# voltage_sensor_v0_4.net
KiCad netlist of a schematic drawn in EAGLE
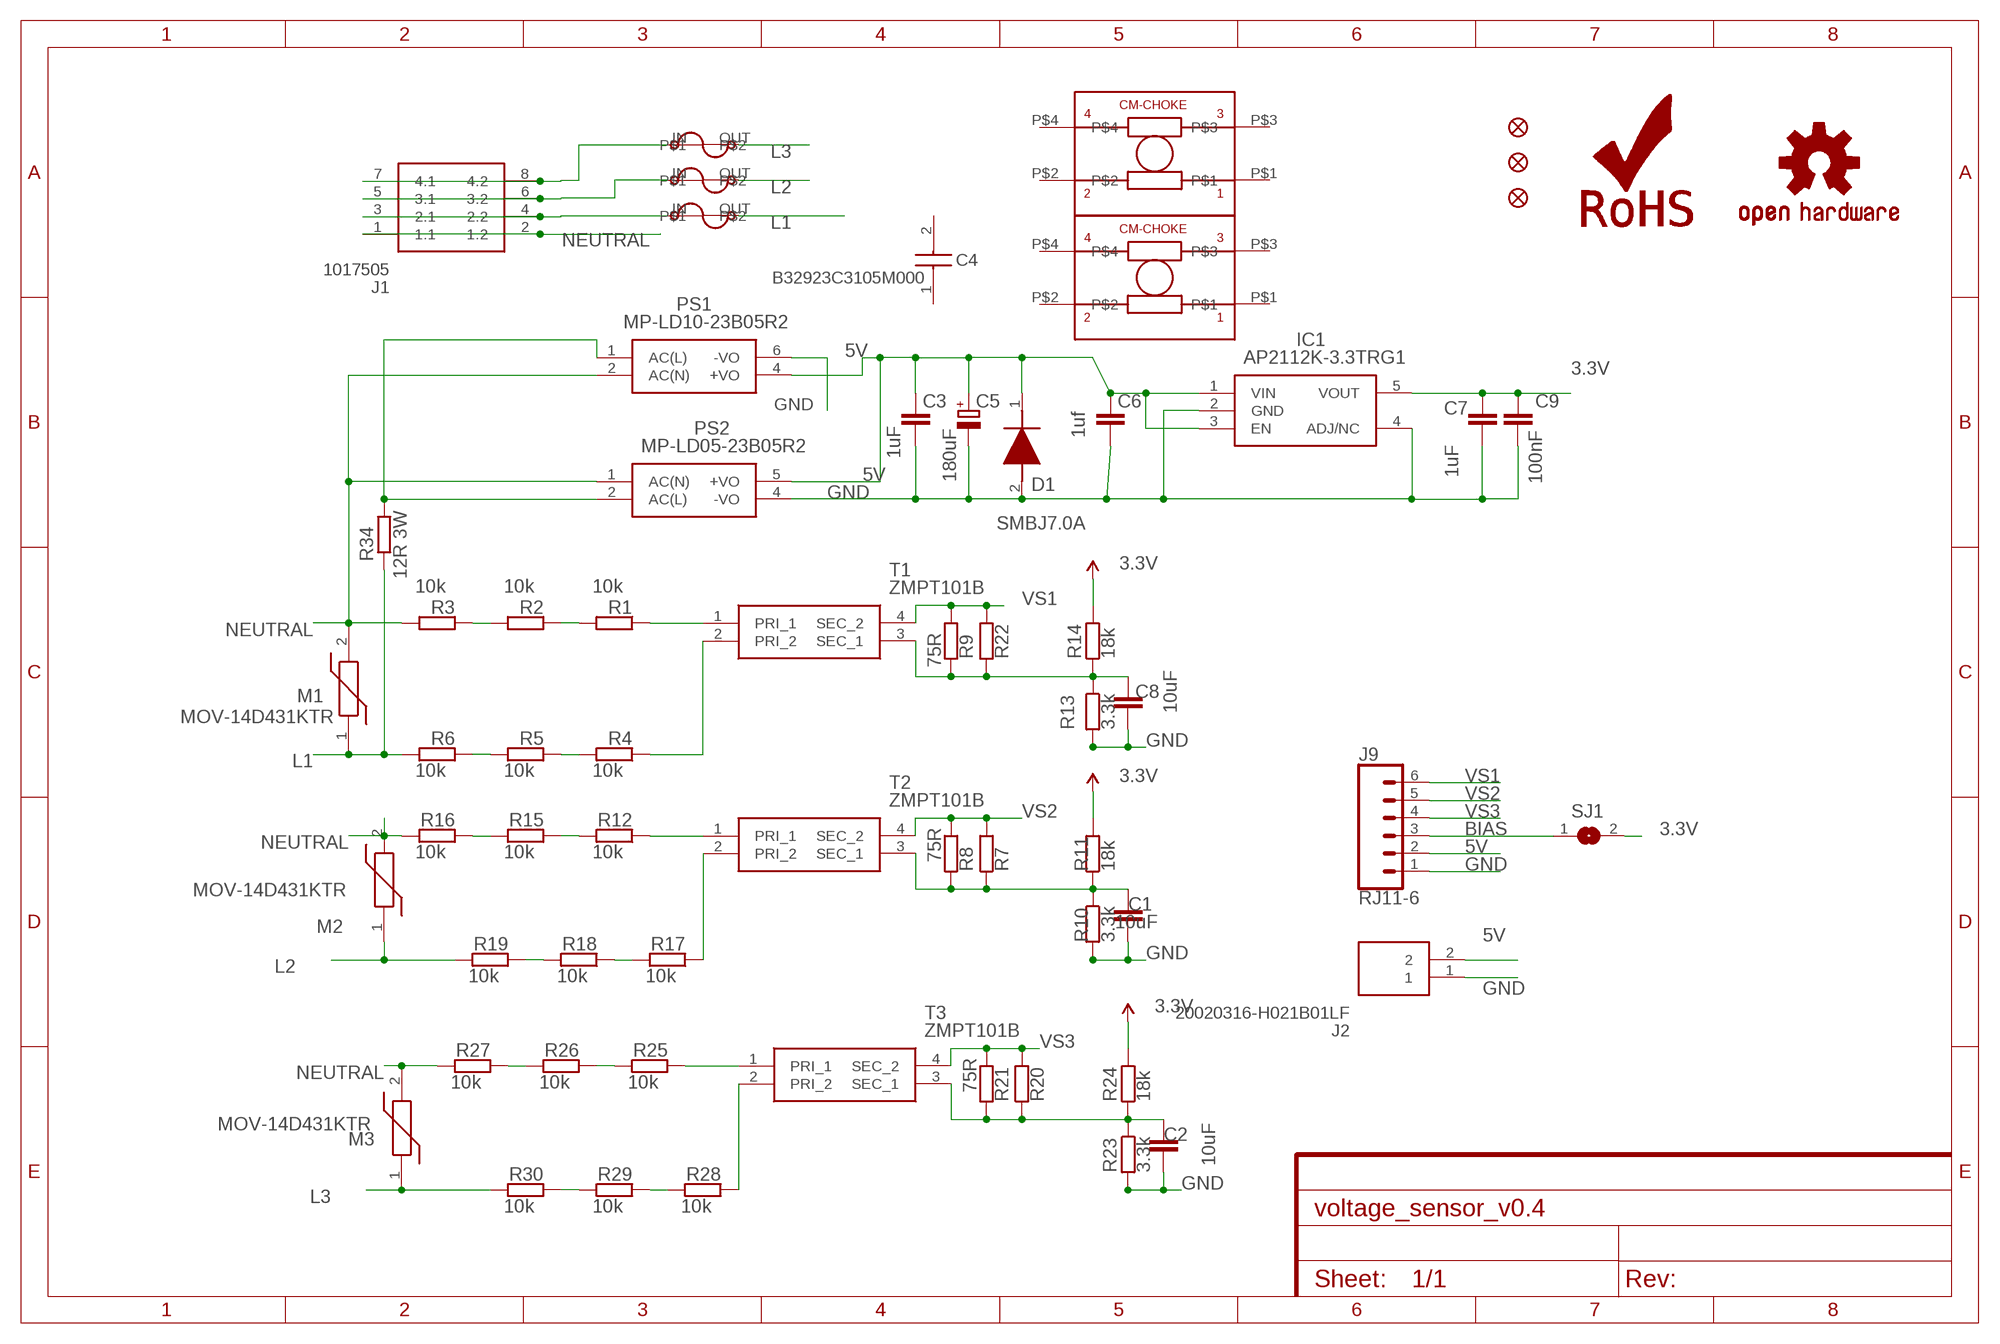
[diagram p0: schematic, sheet 1]

(export (version "E")
  (design (tool "Eeschema 10.0.6"))
  (components
    (comp (ref "C1")
      (value "10uF")
      (footprint "eagle-import:C0603")
      (libsource (lib "eagle-import") (part "C-EUC0603"))
    )
    (comp (ref "C2")
      (value "10uF")
      (footprint "eagle-import:C0603")
      (libsource (lib "eagle-import") (part "C-EUC0603"))
    )
    (comp (ref "C3")
      (value "1uF")
      (footprint "eagle-import:C0603")
      (libsource (lib "eagle-import") (part "C-EUC0603"))
    )
    (comp (ref "C4")
      (value "B32923C3105M000")
      (footprint "eagle-import:B32923C_(26.5_X_12)")
      (libsource (lib "eagle-import") (part "B32923C3105M000"))
    )
    (comp (ref "C5")
      (value "180uF")
      (footprint "eagle-import:PANASONIC_C")
      (libsource (lib "eagle-import") (part "CPOL-EUC"))
    )
    (comp (ref "C6")
      (value "1uf")
      (footprint "eagle-import:C0603")
      (libsource (lib "eagle-import") (part "C-EUC0603"))
    )
    (comp (ref "C7")
      (value "1uF")
      (footprint "eagle-import:C0603")
      (libsource (lib "eagle-import") (part "C-EUC0603"))
    )
    (comp (ref "C8")
      (value "10uF")
      (footprint "eagle-import:C0603")
      (libsource (lib "eagle-import") (part "C-EUC0603"))
    )
    (comp (ref "C9")
      (value "100nF")
      (footprint "eagle-import:C0603")
      (libsource (lib "eagle-import") (part "C-EUC0603"))
    )
    (comp (ref "D1")
      (value "SMBJ7.0A")
      (footprint "eagle-import:DIOM5336X244N")
      (libsource (lib "eagle-import") (part "SMBJ7.0A"))
    )
    (comp (ref "F1")
      (value "2A/250V")
      (footprint "eagle-import:BELFUSE1A")
      (libsource (lib "eagle-import") (part "BEL1AFUSE"))
    )
    (comp (ref "F2")
      (value "2A/250V")
      (footprint "eagle-import:BELFUSE1A")
      (libsource (lib "eagle-import") (part "BEL1AFUSE"))
    )
    (comp (ref "F3")
      (value "2A/250V")
      (footprint "eagle-import:BELFUSE1A")
      (libsource (lib "eagle-import") (part "BEL1AFUSE"))
    )
    (comp (ref "FD1")
      (value "FIDUCIAL1X2")
      (footprint "eagle-import:FIDUCIAL-1X2")
      (libsource (lib "eagle-import") (part "FIDUCIAL1X2"))
    )
    (comp (ref "FD2")
      (value "FIDUCIAL1X2")
      (footprint "eagle-import:FIDUCIAL-1X2")
      (libsource (lib "eagle-import") (part "FIDUCIAL1X2"))
    )
    (comp (ref "FD3")
      (value "FIDUCIAL1X2")
      (footprint "eagle-import:FIDUCIAL-1X2")
      (libsource (lib "eagle-import") (part "FIDUCIAL1X2"))
    )
    (comp (ref "IC1")
      (value "AP2112K-3.3TRG1")
      (footprint "eagle-import:SOT95P282X130-5N")
      (fields (field (name "MOUSER_PART_NUMBER") "621-AP2112K-3.3TRG1"))
      (libsource (lib "eagle-import") (part "AP2112K-3.3TRG1"))
    )
    (comp (ref "J1")
      (value "1017505")
      (footprint "eagle-import:1017505")
      (fields (field (name "MOUSER_PART_NUMBER") "651-1017505"))
      (libsource (lib "eagle-import") (part "1017505"))
    )
    (comp (ref "J2")
      (value "20020316-H021B01LF")
      (footprint "eagle-import:20020316H021B01LF")
      (libsource (lib "eagle-import") (part "20020316-H021B01LF"))
    )
    (comp (ref "J9")
      (value "RJ11-6")
      (footprint "eagle-import:RJ11-6")
      (libsource (lib "eagle-import") (part "RJ11-6"))
    )
    (comp (ref "LOGO1")
      (value "ROHS_LOGO")
      (footprint "eagle-import:ROHS_LOGO_0.18_IN")
      (libsource (lib "eagle-import") (part "ROHS_LOGO"))
    )
    (comp (ref "LOGO2")
      (value "OSHW-LOGOS-COPPER")
      (footprint "eagle-import:OSHW-LOGO-S_COPPER")
      (libsource (lib "eagle-import") (part "OSHW-LOGOS-COPPER"))
    )
    (comp (ref "M1")
      (value "MOV-14D431KTR")
      (footprint "eagle-import:MOV14D431KTR")
      (fields (field (name "MOUSER_PART_NUMBER") "652-MOV-14D431KTR"))
      (libsource (lib "eagle-import") (part "MOV-14D431KTR"))
    )
    (comp (ref "M2")
      (value "MOV-14D431KTR")
      (footprint "eagle-import:MOV14D431KTR")
      (fields (field (name "MOUSER_PART_NUMBER") "652-MOV-14D431KTR"))
      (libsource (lib "eagle-import") (part "MOV-14D431KTR"))
    )
    (comp (ref "M3")
      (value "MOV-14D431KTR")
      (footprint "eagle-import:MOV14D431KTR")
      (fields (field (name "MOUSER_PART_NUMBER") "652-MOV-14D431KTR"))
      (libsource (lib "eagle-import") (part "MOV-14D431KTR"))
    )
    (comp (ref "PS1")
      (value "MP-LD10-23B05R2")
      (footprint "eagle-import:MPLD1023B12R2")
      (libsource (lib "eagle-import") (part "MP-LD10-23B12R2"))
    )
    (comp (ref "PS2")
      (value "MP-LD05-23B05R2")
      (footprint "eagle-import:MPLD0523B03R2")
      (fields (field (name "MANUFACTURER_PART_NUMBER") "MP-LD05-23B03R2"))
      (libsource (lib "eagle-import") (part "MP-LD05-23B03R2"))
    )
    (comp (ref "R1")
      (value "10k")
      (footprint "eagle-import:R0603")
      (libsource (lib "eagle-import") (part "R-EU_R0603"))
    )
    (comp (ref "R2")
      (value "10k")
      (footprint "eagle-import:R0603")
      (libsource (lib "eagle-import") (part "R-EU_R0603"))
    )
    (comp (ref "R3")
      (value "10k")
      (footprint "eagle-import:R0603")
      (libsource (lib "eagle-import") (part "R-EU_R0603"))
    )
    (comp (ref "R4")
      (value "10k")
      (footprint "eagle-import:R0603")
      (libsource (lib "eagle-import") (part "R-EU_R0603"))
    )
    (comp (ref "R5")
      (value "10k")
      (footprint "eagle-import:R0603")
      (libsource (lib "eagle-import") (part "R-EU_R0603"))
    )
    (comp (ref "R6")
      (value "10k")
      (footprint "eagle-import:R0603")
      (libsource (lib "eagle-import") (part "R-EU_R0603"))
    )
    (comp (ref "R7")
      (value "R-EU_0204/7")
      (footprint "eagle-import:0204_7")
      (libsource (lib "eagle-import") (part "R-EU_0204/7"))
    )
    (comp (ref "R8")
      (value "75R")
      (footprint "eagle-import:R0603")
      (libsource (lib "eagle-import") (part "R-EU_R0603"))
    )
    (comp (ref "R9")
      (value "75R")
      (footprint "eagle-import:R0603")
      (libsource (lib "eagle-import") (part "R-EU_R0603"))
    )
    (comp (ref "R10")
      (value "3.3k")
      (footprint "eagle-import:R0603")
      (libsource (lib "eagle-import") (part "R-EU_R0603"))
    )
    (comp (ref "R11")
      (value "18k")
      (footprint "eagle-import:R0603")
      (libsource (lib "eagle-import") (part "R-EU_R0603"))
    )
    (comp (ref "R12")
      (value "10k")
      (footprint "eagle-import:R0603")
      (libsource (lib "eagle-import") (part "R-EU_R0603"))
    )
    (comp (ref "R13")
      (value "3.3k")
      (footprint "eagle-import:R0603")
      (libsource (lib "eagle-import") (part "R-EU_R0603"))
    )
    (comp (ref "R14")
      (value "18k")
      (footprint "eagle-import:R0603")
      (libsource (lib "eagle-import") (part "R-EU_R0603"))
    )
    (comp (ref "R15")
      (value "10k")
      (footprint "eagle-import:R0603")
      (libsource (lib "eagle-import") (part "R-EU_R0603"))
    )
    (comp (ref "R16")
      (value "10k")
      (footprint "eagle-import:R0603")
      (libsource (lib "eagle-import") (part "R-EU_R0603"))
    )
    (comp (ref "R17")
      (value "10k")
      (footprint "eagle-import:R0603")
      (libsource (lib "eagle-import") (part "R-EU_R0603"))
    )
    (comp (ref "R18")
      (value "10k")
      (footprint "eagle-import:R0603")
      (libsource (lib "eagle-import") (part "R-EU_R0603"))
    )
    (comp (ref "R19")
      (value "10k")
      (footprint "eagle-import:R0603")
      (libsource (lib "eagle-import") (part "R-EU_R0603"))
    )
    (comp (ref "R20")
      (value "R-EU_0204/7")
      (footprint "eagle-import:0204_7")
      (libsource (lib "eagle-import") (part "R-EU_0204/7"))
    )
    (comp (ref "R21")
      (value "75R")
      (footprint "eagle-import:R0603")
      (libsource (lib "eagle-import") (part "R-EU_R0603"))
    )
    (comp (ref "R22")
      (value "R-EU_0204/7")
      (footprint "eagle-import:0204_7")
      (libsource (lib "eagle-import") (part "R-EU_0204/7"))
    )
    (comp (ref "R23")
      (value "3.3k")
      (footprint "eagle-import:R0603")
      (libsource (lib "eagle-import") (part "R-EU_R0603"))
    )
    (comp (ref "R24")
      (value "18k")
      (footprint "eagle-import:R0603")
      (libsource (lib "eagle-import") (part "R-EU_R0603"))
    )
    (comp (ref "R25")
      (value "10k")
      (footprint "eagle-import:R0603")
      (libsource (lib "eagle-import") (part "R-EU_R0603"))
    )
    (comp (ref "R26")
      (value "10k")
      (footprint "eagle-import:R0603")
      (libsource (lib "eagle-import") (part "R-EU_R0603"))
    )
    (comp (ref "R27")
      (value "10k")
      (footprint "eagle-import:R0603")
      (libsource (lib "eagle-import") (part "R-EU_R0603"))
    )
    (comp (ref "R28")
      (value "10k")
      (footprint "eagle-import:R0603")
      (libsource (lib "eagle-import") (part "R-EU_R0603"))
    )
    (comp (ref "R29")
      (value "10k")
      (footprint "eagle-import:R0603")
      (libsource (lib "eagle-import") (part "R-EU_R0603"))
    )
    (comp (ref "R30")
      (value "10k")
      (footprint "eagle-import:R0603")
      (libsource (lib "eagle-import") (part "R-EU_R0603"))
    )
    (comp (ref "R34")
      (value "12R 3W")
      (footprint "eagle-import:R2512")
      (libsource (lib "eagle-import") (part "rcl_334_R-EU_R2512"))
    )
    (comp (ref "SJ1") (value "SJ") (footprint "eagle-import:SJ") (libsource (lib "eagle-import") (part "SJ")))
    (comp (ref "T1")
      (value "ZMPT101B")
      (footprint "eagle-import:ZMPT101B")
      (libsource (lib "eagle-import") (part "ZMPT101B"))
    )
    (comp (ref "T2")
      (value "ZMPT101B")
      (footprint "eagle-import:ZMPT101B")
      (libsource (lib "eagle-import") (part "ZMPT101B"))
    )
    (comp (ref "T3")
      (value "ZMPT101B")
      (footprint "eagle-import:ZMPT101B")
      (libsource (lib "eagle-import") (part "ZMPT101B"))
    )
    (comp (ref "U$1")
      (value "47mH")
      (footprint "eagle-import:RN114-0.3-02-47M")
      (libsource (lib "eagle-import") (part "RN114-0.3-02-47M"))
    )
    (comp (ref "U$2")
      (value "RN214-0.3-02-47M")
      (footprint "eagle-import:RN214-0.3-02-47M")
      (libsource (lib "eagle-import") (part "RN214-0.3-02-47M"))
    )
  )
  (nets
    (net (code "1") (name "/5V") (class "Default")
      (node (ref "C3") (pin "1") (pinfunction "1_1") (pintype "passive"))
      (node (ref "C5") (pin "+") (pinfunction "+_+") (pintype "passive"))
      (node (ref "C6") (pin "1") (pinfunction "1_1") (pintype "passive"))
      (node (ref "D1") (pin "1") (pinfunction "K_1") (pintype "bidirectional"))
      (node (ref "IC1") (pin "1") (pinfunction "VIN_1") (pintype "bidirectional"))
      (node (ref "IC1") (pin "3") (pinfunction "EN_3") (pintype "bidirectional"))
      (node (ref "J2") (pin "2") (pinfunction "2_2") (pintype "bidirectional"))
      (node (ref "J9") (pin "2") (pinfunction "2_2") (pintype "passive"))
      (node (ref "PS1") (pin "4") (pinfunction "+VO_4") (pintype "bidirectional"))
      (node (ref "PS2") (pin "5") (pinfunction "+VO_5") (pintype "bidirectional"))
    )
    (net (code "2") (name "/BIAS") (class "Default")
      (node (ref "J9") (pin "3") (pinfunction "3_3") (pintype "passive"))
      (node (ref "SJ1") (pin "1") (pinfunction "1_1") (pintype "passive"))
    )
    (net (code "3") (name "/GND") (class "Default")
      (node (ref "C1") (pin "2") (pinfunction "2_2") (pintype "passive"))
      (node (ref "C2") (pin "2") (pinfunction "2_2") (pintype "passive"))
      (node (ref "C3") (pin "2") (pinfunction "2_2") (pintype "passive"))
      (node (ref "C5") (pin "-") (pinfunction "-_-") (pintype "passive"))
      (node (ref "C6") (pin "2") (pinfunction "2_2") (pintype "passive"))
      (node (ref "C7") (pin "2") (pinfunction "2_2") (pintype "passive"))
      (node (ref "C8") (pin "2") (pinfunction "2_2") (pintype "passive"))
      (node (ref "C9") (pin "2") (pinfunction "2_2") (pintype "passive"))
      (node (ref "D1") (pin "2") (pinfunction "A_2") (pintype "bidirectional"))
      (node (ref "IC1") (pin "2") (pinfunction "GND_2") (pintype "bidirectional"))
      (node (ref "IC1") (pin "4") (pinfunction "ADJ/NC_4") (pintype "bidirectional"))
      (node (ref "J2") (pin "1") (pinfunction "1_1") (pintype "bidirectional"))
      (node (ref "J9") (pin "1") (pinfunction "1_1") (pintype "passive"))
      (node (ref "PS1") (pin "6") (pinfunction "-VO_6") (pintype "bidirectional"))
      (node (ref "PS2") (pin "4") (pinfunction "-VO_4") (pintype "bidirectional"))
      (node (ref "R10") (pin "2") (pinfunction "2_2") (pintype "passive"))
      (node (ref "R13") (pin "2") (pinfunction "2_2") (pintype "passive"))
      (node (ref "R23") (pin "2") (pinfunction "2_2") (pintype "passive"))
    )
    (net (code "4") (name "/L1") (class "Default")
      (node (ref "F1") (pin "OUT") (pinfunction "P$1_OUT") (pintype "bidirectional"))
      (node (ref "M1") (pin "1") (pinfunction "1_1") (pintype "bidirectional"))
      (node (ref "R34") (pin "1") (pinfunction "1_1") (pintype "passive"))
      (node (ref "R6") (pin "2") (pinfunction "2_2") (pintype "passive"))
    )
    (net (code "5") (name "/L2") (class "Default")
      (node (ref "F2") (pin "OUT") (pinfunction "P$1_OUT") (pintype "bidirectional"))
      (node (ref "M2") (pin "1") (pinfunction "1_1") (pintype "bidirectional"))
      (node (ref "R19") (pin "2") (pinfunction "2_2") (pintype "passive"))
    )
    (net (code "6") (name "/L3") (class "Default")
      (node (ref "F3") (pin "OUT") (pinfunction "P$1_OUT") (pintype "bidirectional"))
      (node (ref "M3") (pin "1") (pinfunction "1_1") (pintype "bidirectional"))
      (node (ref "R30") (pin "2") (pinfunction "2_2") (pintype "passive"))
    )
    (net (code "7") (name "/NEUTRAL") (class "Default")
      (node (ref "J1") (pin "1") (pinfunction "1.1_1") (pintype "bidirectional"))
      (node (ref "J1") (pin "2") (pinfunction "1.2_2") (pintype "bidirectional"))
      (node (ref "M1") (pin "2") (pinfunction "2_2") (pintype "bidirectional"))
      (node (ref "M2") (pin "2") (pinfunction "2_2") (pintype "bidirectional"))
      (node (ref "M3") (pin "2") (pinfunction "2_2") (pintype "bidirectional"))
      (node (ref "PS1") (pin "2") (pinfunction "AC(N)_2") (pintype "bidirectional"))
      (node (ref "PS2") (pin "1") (pinfunction "AC(N)_1") (pintype "bidirectional"))
      (node (ref "R16") (pin "2") (pinfunction "2_2") (pintype "passive"))
      (node (ref "R27") (pin "2") (pinfunction "2_2") (pintype "passive"))
      (node (ref "R3") (pin "2") (pinfunction "2_2") (pintype "passive"))
    )
    (net (code "8") (name "/VS1") (class "Default")
      (node (ref "J9") (pin "6") (pinfunction "6_6") (pintype "passive"))
      (node (ref "R22") (pin "2") (pinfunction "2_2") (pintype "passive"))
      (node (ref "R9") (pin "2") (pinfunction "2_2") (pintype "passive"))
      (node (ref "T1") (pin "4") (pinfunction "SEC_2_4") (pintype "bidirectional"))
    )
    (net (code "9") (name "/VS2") (class "Default")
      (node (ref "J9") (pin "5") (pinfunction "5_5") (pintype "passive"))
      (node (ref "R7") (pin "2") (pinfunction "2_2") (pintype "passive"))
      (node (ref "R8") (pin "2") (pinfunction "2_2") (pintype "passive"))
      (node (ref "T2") (pin "4") (pinfunction "SEC_2_4") (pintype "bidirectional"))
    )
    (net (code "10") (name "/VS3") (class "Default")
      (node (ref "J9") (pin "4") (pinfunction "4_4") (pintype "passive"))
      (node (ref "R20") (pin "2") (pinfunction "2_2") (pintype "passive"))
      (node (ref "R21") (pin "2") (pinfunction "2_2") (pintype "passive"))
      (node (ref "T3") (pin "4") (pinfunction "SEC_2_4") (pintype "bidirectional"))
    )
    (net (code "11") (name "3.3V") (class "Default")
      (node (ref "C7") (pin "1") (pinfunction "1_1") (pintype "passive"))
      (node (ref "C9") (pin "1") (pinfunction "1_1") (pintype "passive"))
      (node (ref "IC1") (pin "5") (pinfunction "VOUT_5") (pintype "bidirectional"))
      (node (ref "R11") (pin "2") (pinfunction "2_2") (pintype "passive"))
      (node (ref "R14") (pin "2") (pinfunction "2_2") (pintype "passive"))
      (node (ref "R24") (pin "2") (pinfunction "2_2") (pintype "passive"))
      (node (ref "SJ1") (pin "2") (pinfunction "2_2") (pintype "passive"))
    )
    (net (code "12") (name "Net-(F1-P$2)") (class "Default")
      (node (ref "F1") (pin "IN") (pinfunction "P$2_IN") (pintype "bidirectional"))
      (node (ref "J1") (pin "3") (pinfunction "2.1_3") (pintype "bidirectional"))
      (node (ref "J1") (pin "4") (pinfunction "2.2_4") (pintype "bidirectional"))
    )
    (net (code "13") (name "Net-(F2-P$2)") (class "Default")
      (node (ref "F2") (pin "IN") (pinfunction "P$2_IN") (pintype "bidirectional"))
      (node (ref "J1") (pin "5") (pinfunction "3.1_5") (pintype "bidirectional"))
      (node (ref "J1") (pin "6") (pinfunction "3.2_6") (pintype "bidirectional"))
    )
    (net (code "14") (name "Net-(F3-P$2)") (class "Default")
      (node (ref "F3") (pin "IN") (pinfunction "P$2_IN") (pintype "bidirectional"))
      (node (ref "J1") (pin "7") (pinfunction "4.1_7") (pintype "bidirectional"))
      (node (ref "J1") (pin "8") (pinfunction "4.2_8") (pintype "bidirectional"))
    )
    (net (code "15") (name "Net-(PS1-AC(L))") (class "Default")
      (node (ref "PS1") (pin "1") (pinfunction "AC(L)_1") (pintype "bidirectional"))
      (node (ref "PS2") (pin "2") (pinfunction "AC(L)_2") (pintype "bidirectional"))
      (node (ref "R34") (pin "2") (pinfunction "2_2") (pintype "passive"))
    )
    (net (code "16") (name "Net-(R1-Pad2)") (class "Default")
      (node (ref "R1") (pin "2") (pinfunction "2_2") (pintype "passive"))
      (node (ref "R2") (pin "1") (pinfunction "1_1") (pintype "passive"))
    )
    (net (code "17") (name "Net-(R2-Pad2)") (class "Default")
      (node (ref "R2") (pin "2") (pinfunction "2_2") (pintype "passive"))
      (node (ref "R3") (pin "1") (pinfunction "1_1") (pintype "passive"))
    )
    (net (code "18") (name "Net-(R4-Pad2)") (class "Default")
      (node (ref "R4") (pin "2") (pinfunction "2_2") (pintype "passive"))
      (node (ref "R5") (pin "1") (pinfunction "1_1") (pintype "passive"))
    )
    (net (code "19") (name "Net-(R5-Pad2)") (class "Default")
      (node (ref "R5") (pin "2") (pinfunction "2_2") (pintype "passive"))
      (node (ref "R6") (pin "1") (pinfunction "1_1") (pintype "passive"))
    )
    (net (code "20") (name "Net-(R12-Pad2)") (class "Default")
      (node (ref "R12") (pin "2") (pinfunction "2_2") (pintype "passive"))
      (node (ref "R15") (pin "1") (pinfunction "1_1") (pintype "passive"))
    )
    (net (code "21") (name "Net-(R15-Pad2)") (class "Default")
      (node (ref "R15") (pin "2") (pinfunction "2_2") (pintype "passive"))
      (node (ref "R16") (pin "1") (pinfunction "1_1") (pintype "passive"))
    )
    (net (code "22") (name "Net-(R17-Pad2)") (class "Default")
      (node (ref "R17") (pin "2") (pinfunction "2_2") (pintype "passive"))
      (node (ref "R18") (pin "1") (pinfunction "1_1") (pintype "passive"))
    )
    (net (code "23") (name "Net-(R18-Pad2)") (class "Default")
      (node (ref "R18") (pin "2") (pinfunction "2_2") (pintype "passive"))
      (node (ref "R19") (pin "1") (pinfunction "1_1") (pintype "passive"))
    )
    (net (code "24") (name "Net-(R25-Pad2)") (class "Default")
      (node (ref "R25") (pin "2") (pinfunction "2_2") (pintype "passive"))
      (node (ref "R26") (pin "1") (pinfunction "1_1") (pintype "passive"))
    )
    (net (code "25") (name "Net-(R26-Pad2)") (class "Default")
      (node (ref "R26") (pin "2") (pinfunction "2_2") (pintype "passive"))
      (node (ref "R27") (pin "1") (pinfunction "1_1") (pintype "passive"))
    )
    (net (code "26") (name "Net-(R28-Pad2)") (class "Default")
      (node (ref "R28") (pin "2") (pinfunction "2_2") (pintype "passive"))
      (node (ref "R29") (pin "1") (pinfunction "1_1") (pintype "passive"))
    )
    (net (code "27") (name "Net-(R29-Pad2)") (class "Default")
      (node (ref "R29") (pin "2") (pinfunction "2_2") (pintype "passive"))
      (node (ref "R30") (pin "1") (pinfunction "1_1") (pintype "passive"))
    )
    (net (code "28") (name "Net-(T1-PRI_1)") (class "Default")
      (node (ref "R1") (pin "1") (pinfunction "1_1") (pintype "passive"))
      (node (ref "T1") (pin "1") (pinfunction "PRI_1_1") (pintype "bidirectional"))
    )
    (net (code "29") (name "Net-(T1-PRI_2)") (class "Default")
      (node (ref "R4") (pin "1") (pinfunction "1_1") (pintype "passive"))
      (node (ref "T1") (pin "2") (pinfunction "PRI_2_2") (pintype "bidirectional"))
    )
    (net (code "30") (name "Net-(T1-SEC_1)") (class "Default")
      (node (ref "C8") (pin "1") (pinfunction "1_1") (pintype "passive"))
      (node (ref "R13") (pin "1") (pinfunction "1_1") (pintype "passive"))
      (node (ref "R14") (pin "1") (pinfunction "1_1") (pintype "passive"))
      (node (ref "R22") (pin "1") (pinfunction "1_1") (pintype "passive"))
      (node (ref "R9") (pin "1") (pinfunction "1_1") (pintype "passive"))
      (node (ref "T1") (pin "3") (pinfunction "SEC_1_3") (pintype "bidirectional"))
    )
    (net (code "31") (name "Net-(T2-PRI_1)") (class "Default")
      (node (ref "R12") (pin "1") (pinfunction "1_1") (pintype "passive"))
      (node (ref "T2") (pin "1") (pinfunction "PRI_1_1") (pintype "bidirectional"))
    )
    (net (code "32") (name "Net-(T2-PRI_2)") (class "Default")
      (node (ref "R17") (pin "1") (pinfunction "1_1") (pintype "passive"))
      (node (ref "T2") (pin "2") (pinfunction "PRI_2_2") (pintype "bidirectional"))
    )
    (net (code "33") (name "Net-(T2-SEC_1)") (class "Default")
      (node (ref "C1") (pin "1") (pinfunction "1_1") (pintype "passive"))
      (node (ref "R10") (pin "1") (pinfunction "1_1") (pintype "passive"))
      (node (ref "R11") (pin "1") (pinfunction "1_1") (pintype "passive"))
      (node (ref "R7") (pin "1") (pinfunction "1_1") (pintype "passive"))
      (node (ref "R8") (pin "1") (pinfunction "1_1") (pintype "passive"))
      (node (ref "T2") (pin "3") (pinfunction "SEC_1_3") (pintype "bidirectional"))
    )
    (net (code "34") (name "Net-(T3-PRI_1)") (class "Default")
      (node (ref "R25") (pin "1") (pinfunction "1_1") (pintype "passive"))
      (node (ref "T3") (pin "1") (pinfunction "PRI_1_1") (pintype "bidirectional"))
    )
    (net (code "35") (name "Net-(T3-PRI_2)") (class "Default")
      (node (ref "R28") (pin "1") (pinfunction "1_1") (pintype "passive"))
      (node (ref "T3") (pin "2") (pinfunction "PRI_2_2") (pintype "bidirectional"))
    )
    (net (code "36") (name "Net-(T3-SEC_1)") (class "Default")
      (node (ref "C2") (pin "1") (pinfunction "1_1") (pintype "passive"))
      (node (ref "R20") (pin "1") (pinfunction "1_1") (pintype "passive"))
      (node (ref "R21") (pin "1") (pinfunction "1_1") (pintype "passive"))
      (node (ref "R23") (pin "1") (pinfunction "1_1") (pintype "passive"))
      (node (ref "R24") (pin "1") (pinfunction "1_1") (pintype "passive"))
      (node (ref "T3") (pin "3") (pinfunction "SEC_1_3") (pintype "bidirectional"))
    )
    (net (code "37") (name "unconnected-(C4-Pad1)") (class "Default")
      (node (ref "C4") (pin "1") (pinfunction "1_1") (pintype "bidirectional"))
    )
    (net (code "38") (name "unconnected-(C4-Pad2)") (class "Default")
      (node (ref "C4") (pin "2") (pinfunction "2_2") (pintype "bidirectional"))
    )
    (net (code "39") (name "unconnected-(U$1-PadP$1)") (class "Default")
      (node (ref "U$1") (pin "P$1") (pinfunction "P$1_P$1") (pintype "bidirectional"))
    )
    (net (code "40") (name "unconnected-(U$1-PadP$2)") (class "Default")
      (node (ref "U$1") (pin "P$2") (pinfunction "P$2_P$2") (pintype "bidirectional"))
    )
    (net (code "41") (name "unconnected-(U$1-PadP$3)") (class "Default")
      (node (ref "U$1") (pin "P$3") (pinfunction "P$3_P$3") (pintype "bidirectional"))
    )
    (net (code "42") (name "unconnected-(U$1-PadP$4)") (class "Default")
      (node (ref "U$1") (pin "P$4") (pinfunction "P$4_P$4") (pintype "bidirectional"))
    )
    (net (code "43") (name "unconnected-(U$2-PadP$1)") (class "Default")
      (node (ref "U$2") (pin "P$1") (pinfunction "P$1_P$1") (pintype "bidirectional"))
    )
    (net (code "44") (name "unconnected-(U$2-PadP$2)") (class "Default")
      (node (ref "U$2") (pin "P$2") (pinfunction "P$2_P$2") (pintype "bidirectional"))
    )
    (net (code "45") (name "unconnected-(U$2-PadP$3)") (class "Default")
      (node (ref "U$2") (pin "P$3") (pinfunction "P$3_P$3") (pintype "bidirectional"))
    )
    (net (code "46") (name "unconnected-(U$2-PadP$4)") (class "Default")
      (node (ref "U$2") (pin "P$4") (pinfunction "P$4_P$4") (pintype "bidirectional"))
    )
  )
)
